# IV_Swinger_2_ss_cell.net
KiCad netlist of a schematic drawn in EAGLE
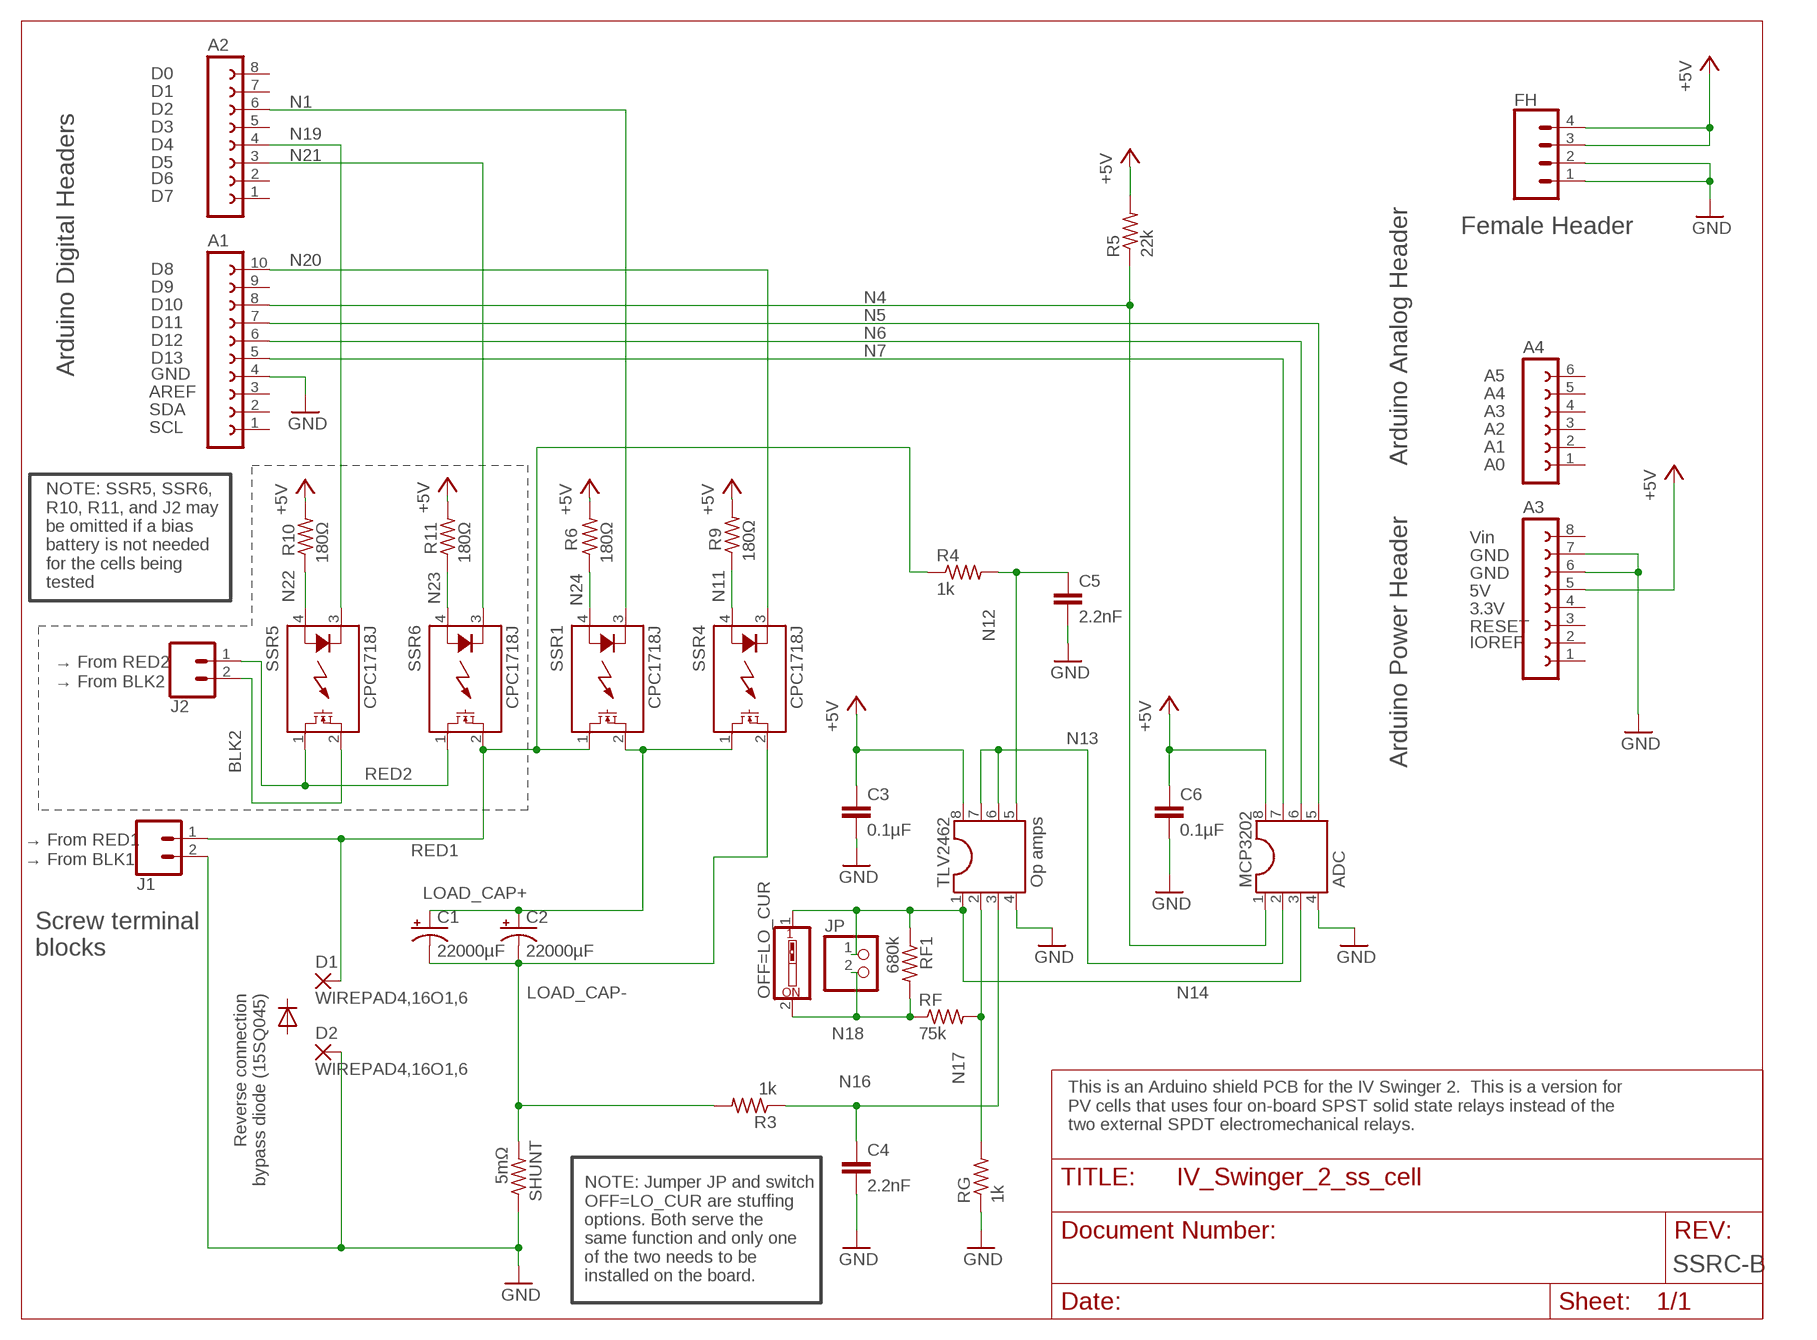
[diagram p0: schematic, sheet 1]

(export (version "E")
  (design (tool "Eeschema 10.0.6"))
  (components
    (comp (ref "A1")
      (value "FE10-1")
      (footprint "eagle-import:FE10")
      (libsource (lib "eagle-import") (part "FE10-1"))
    )
    (comp (ref "A2")
      (value "FE08-1")
      (footprint "eagle-import:FE08")
      (libsource (lib "eagle-import") (part "FE08-1"))
    )
    (comp (ref "A3")
      (value "FE08-1")
      (footprint "eagle-import:FE08")
      (libsource (lib "eagle-import") (part "FE08-1"))
    )
    (comp (ref "A4")
      (value "FE06-1")
      (footprint "eagle-import:FE06")
      (libsource (lib "eagle-import") (part "FE06-1"))
    )
    (comp (ref "C1")
      (value "22000µF")
      (footprint "eagle-import:E7,5-18")
      (libsource (lib "eagle-import") (part "CPOL-USE7.5-18"))
    )
    (comp (ref "C2")
      (value "22000µF")
      (footprint "eagle-import:E7,5-18")
      (libsource (lib "eagle-import") (part "CPOL-USE7.5-18"))
    )
    (comp (ref "C3")
      (value "0.1µF")
      (footprint "eagle-import:C025-030X050")
      (libsource (lib "eagle-import") (part "C-EU025-030X050"))
    )
    (comp (ref "C4")
      (value "2.2nF")
      (footprint "eagle-import:C025-030X050")
      (libsource (lib "eagle-import") (part "C-EU025-030X050"))
    )
    (comp (ref "C5")
      (value "2.2nF")
      (footprint "eagle-import:C025-030X050")
      (libsource (lib "eagle-import") (part "C-EU025-030X050"))
    )
    (comp (ref "C6")
      (value "0.1µF")
      (footprint "eagle-import:C025-030X050")
      (libsource (lib "eagle-import") (part "C-EU025-030X050"))
    )
    (comp (ref "D1")
      (value "WIREPAD4,16O1,6")
      (footprint "eagle-import:4,16O1,6")
      (fields (field (name "SPICEPREFIX") "X"))
      (libsource (lib "eagle-import") (part "WIREPAD4,16O1,6"))
    )
    (comp (ref "D2")
      (value "WIREPAD4,16O1,6")
      (footprint "eagle-import:4,16O1,6")
      (libsource (lib "eagle-import") (part "WIREPAD4,16O1,6"))
    )
    (comp (ref "FH")
      (value "CONN_04LONGPADS")
      (footprint "eagle-import:1X04_LONGPADS")
      (libsource (lib "eagle-import") (part "CONN_04LONGPADS"))
    )
    (comp (ref "J1")
      (value "CONN_025MM")
      (footprint "eagle-import:SCREWTERMINAL-5MM-2")
      (libsource (lib "eagle-import") (part "CONN_025MM"))
    )
    (comp (ref "J2")
      (value "CONN_025MM")
      (footprint "eagle-import:SCREWTERMINAL-5MM-2")
      (libsource (lib "eagle-import") (part "CONN_025MM"))
    )
    (comp (ref "JP")
      (value "PINHD-1X2")
      (footprint "eagle-import:1X02")
      (libsource (lib "eagle-import") (part "PINHD-1X2"))
    )
    (comp (ref "MCP3202")
      (value "ADC")
      (footprint "eagle-import:SOCKET-08")
      (libsource (lib "eagle-import") (part "DIL8S"))
    )
    (comp (ref "OFF=LO_CUR")
      (value "SW_DIP-1")
      (footprint "eagle-import:EDG-01")
      (libsource (lib "eagle-import") (part "SW_DIP-1"))
    )
    (comp (ref "R3")
      (value "1k")
      (footprint "eagle-import:0207_10")
      (libsource (lib "eagle-import") (part "R-US_0207/10"))
    )
    (comp (ref "R4")
      (value "1k")
      (footprint "eagle-import:0207_10")
      (libsource (lib "eagle-import") (part "R-US_0207/10"))
    )
    (comp (ref "R5")
      (value "22k")
      (footprint "eagle-import:0207_10")
      (libsource (lib "eagle-import") (part "R-US_0207/10"))
    )
    (comp (ref "R6")
      (value "180Ω")
      (footprint "eagle-import:0207_10")
      (libsource (lib "eagle-import") (part "R-US_0207/10"))
    )
    (comp (ref "R9")
      (value "180Ω")
      (footprint "eagle-import:0207_10")
      (libsource (lib "eagle-import") (part "R-US_0207/10"))
    )
    (comp (ref "R10")
      (value "180Ω")
      (footprint "eagle-import:0207_10")
      (libsource (lib "eagle-import") (part "R-US_0207/10"))
    )
    (comp (ref "R11")
      (value "180Ω")
      (footprint "eagle-import:0207_10")
      (libsource (lib "eagle-import") (part "R-US_0207/10"))
    )
    (comp (ref "RF")
      (value "75k")
      (footprint "eagle-import:0207_10")
      (libsource (lib "eagle-import") (part "R-US_0207/10"))
    )
    (comp (ref "RF1")
      (value "680k")
      (footprint "eagle-import:0207_10")
      (libsource (lib "eagle-import") (part "R-US_0207/10"))
    )
    (comp (ref "RG")
      (value "1k")
      (footprint "eagle-import:0207_10")
      (libsource (lib "eagle-import") (part "R-US_0207/10"))
    )
    (comp (ref "SHUNT")
      (value "5mΩ")
      (footprint "eagle-import:0617_17")
      (libsource (lib "eagle-import") (part "R-US_0617/17"))
    )
    (comp (ref "SSR1")
      (value "CPC1718J")
      (footprint "eagle-import:I4-PAC")
      (libsource (lib "eagle-import") (part "CPC1718J"))
    )
    (comp (ref "SSR4")
      (value "CPC1718J")
      (footprint "eagle-import:I4-PAC")
      (libsource (lib "eagle-import") (part "CPC1718J"))
    )
    (comp (ref "SSR5")
      (value "CPC1718J")
      (footprint "eagle-import:I4-PAC")
      (libsource (lib "eagle-import") (part "CPC1718J"))
    )
    (comp (ref "SSR6")
      (value "CPC1718J")
      (footprint "eagle-import:I4-PAC")
      (libsource (lib "eagle-import") (part "CPC1718J"))
    )
    (comp (ref "TLV2462")
      (value "Op amps")
      (footprint "eagle-import:SOCKET-08")
      (libsource (lib "eagle-import") (part "DIL8S"))
    )
  )
  (nets
    (net (code "1") (name "+5V") (class "Default")
      (node (ref "A3") (pin "5") (pinfunction "5_5") (pintype "passive"))
      (node (ref "C3") (pin "1") (pinfunction "1_1") (pintype "passive"))
      (node (ref "C6") (pin "1") (pinfunction "1_1") (pintype "passive"))
      (node (ref "FH") (pin "3") (pinfunction "3_3") (pintype "passive"))
      (node (ref "FH") (pin "4") (pinfunction "4_4") (pintype "passive"))
      (node (ref "MCP3202") (pin "8") (pinfunction "8_8") (pintype "passive"))
      (node (ref "R10") (pin "2") (pinfunction "2_2") (pintype "passive"))
      (node (ref "R11") (pin "2") (pinfunction "2_2") (pintype "passive"))
      (node (ref "R5") (pin "2") (pinfunction "2_2") (pintype "passive"))
      (node (ref "R6") (pin "2") (pinfunction "2_2") (pintype "passive"))
      (node (ref "R9") (pin "2") (pinfunction "2_2") (pintype "passive"))
      (node (ref "TLV2462") (pin "8") (pinfunction "8_8") (pintype "passive"))
    )
    (net (code "2") (name "/BLK2") (class "Default")
      (node (ref "J2") (pin "2") (pinfunction "2_2") (pintype "passive"))
      (node (ref "SSR5") (pin "2") (pinfunction "DS2_2") (pintype "passive"))
    )
    (net (code "3") (name "/LOAD_CAP+") (class "Default")
      (node (ref "C1") (pin "+") (pinfunction "+_+") (pintype "passive"))
      (node (ref "C2") (pin "+") (pinfunction "+_+") (pintype "passive"))
      (node (ref "SSR1") (pin "2") (pinfunction "DS2_2") (pintype "passive"))
      (node (ref "SSR4") (pin "1") (pinfunction "DS1_1") (pintype "passive"))
    )
    (net (code "4") (name "/LOAD_CAP-") (class "Default")
      (node (ref "C1") (pin "-") (pinfunction "-_-") (pintype "passive"))
      (node (ref "C2") (pin "-") (pinfunction "-_-") (pintype "passive"))
      (node (ref "R3") (pin "2") (pinfunction "2_2") (pintype "passive"))
      (node (ref "SHUNT") (pin "2") (pinfunction "2_2") (pintype "passive"))
      (node (ref "SSR4") (pin "2") (pinfunction "DS2_2") (pintype "passive"))
    )
    (net (code "5") (name "/N1") (class "Default")
      (node (ref "A2") (pin "6") (pinfunction "6_6") (pintype "passive"))
      (node (ref "SSR1") (pin "3") (pinfunction "K_3") (pintype "passive"))
    )
    (net (code "6") (name "/N4") (class "Default")
      (node (ref "A1") (pin "8") (pinfunction "8_8") (pintype "passive"))
      (node (ref "MCP3202") (pin "1") (pinfunction "1_1") (pintype "passive"))
      (node (ref "R5") (pin "1") (pinfunction "1_1") (pintype "passive"))
    )
    (net (code "7") (name "/N5") (class "Default")
      (node (ref "A1") (pin "7") (pinfunction "7_7") (pintype "passive"))
      (node (ref "MCP3202") (pin "5") (pinfunction "5_5") (pintype "passive"))
    )
    (net (code "8") (name "/N6") (class "Default")
      (node (ref "A1") (pin "6") (pinfunction "6_6") (pintype "passive"))
      (node (ref "MCP3202") (pin "6") (pinfunction "6_6") (pintype "passive"))
    )
    (net (code "9") (name "/N7") (class "Default")
      (node (ref "A1") (pin "5") (pinfunction "5_5") (pintype "passive"))
      (node (ref "MCP3202") (pin "7") (pinfunction "7_7") (pintype "passive"))
    )
    (net (code "10") (name "/N11") (class "Default")
      (node (ref "R9") (pin "1") (pinfunction "1_1") (pintype "passive"))
      (node (ref "SSR4") (pin "4") (pinfunction "A_4") (pintype "passive"))
    )
    (net (code "11") (name "/N12") (class "Default")
      (node (ref "C5") (pin "1") (pinfunction "1_1") (pintype "passive"))
      (node (ref "R4") (pin "2") (pinfunction "2_2") (pintype "passive"))
      (node (ref "TLV2462") (pin "5") (pinfunction "5_5") (pintype "passive"))
    )
    (net (code "12") (name "/N13") (class "Default")
      (node (ref "MCP3202") (pin "2") (pinfunction "2_2") (pintype "passive"))
      (node (ref "TLV2462") (pin "6") (pinfunction "6_6") (pintype "passive"))
      (node (ref "TLV2462") (pin "7") (pinfunction "7_7") (pintype "passive"))
    )
    (net (code "13") (name "/N14") (class "Default")
      (node (ref "JP") (pin "1") (pinfunction "1_1") (pintype "passive"))
      (node (ref "MCP3202") (pin "3") (pinfunction "3_3") (pintype "passive"))
      (node (ref "OFF=LO_CUR") (pin "1") (pinfunction "1_1") (pintype "passive"))
      (node (ref "RF1") (pin "1") (pinfunction "1_1") (pintype "passive"))
      (node (ref "TLV2462") (pin "1") (pinfunction "1_1") (pintype "passive"))
    )
    (net (code "14") (name "/N16") (class "Default")
      (node (ref "C4") (pin "1") (pinfunction "1_1") (pintype "passive"))
      (node (ref "R3") (pin "1") (pinfunction "1_1") (pintype "passive"))
      (node (ref "TLV2462") (pin "3") (pinfunction "3_3") (pintype "passive"))
    )
    (net (code "15") (name "/N17") (class "Default")
      (node (ref "RF") (pin "2") (pinfunction "2_2") (pintype "passive"))
      (node (ref "RG") (pin "2") (pinfunction "2_2") (pintype "passive"))
      (node (ref "TLV2462") (pin "2") (pinfunction "2_2") (pintype "passive"))
    )
    (net (code "16") (name "/N18") (class "Default")
      (node (ref "JP") (pin "2") (pinfunction "2_2") (pintype "passive"))
      (node (ref "OFF=LO_CUR") (pin "2") (pinfunction "2_2") (pintype "passive"))
      (node (ref "RF") (pin "1") (pinfunction "1_1") (pintype "passive"))
      (node (ref "RF1") (pin "2") (pinfunction "2_2") (pintype "passive"))
    )
    (net (code "17") (name "/N19") (class "Default")
      (node (ref "A2") (pin "4") (pinfunction "4_4") (pintype "passive"))
      (node (ref "SSR5") (pin "3") (pinfunction "K_3") (pintype "passive"))
    )
    (net (code "18") (name "/N20") (class "Default")
      (node (ref "A1") (pin "10") (pinfunction "10_10") (pintype "passive"))
      (node (ref "SSR4") (pin "3") (pinfunction "K_3") (pintype "passive"))
    )
    (net (code "19") (name "/N21") (class "Default")
      (node (ref "A2") (pin "3") (pinfunction "3_3") (pintype "passive"))
      (node (ref "SSR6") (pin "3") (pinfunction "K_3") (pintype "passive"))
    )
    (net (code "20") (name "/N22") (class "Default")
      (node (ref "R10") (pin "1") (pinfunction "1_1") (pintype "passive"))
      (node (ref "SSR5") (pin "4") (pinfunction "A_4") (pintype "passive"))
    )
    (net (code "21") (name "/N23") (class "Default")
      (node (ref "R11") (pin "1") (pinfunction "1_1") (pintype "passive"))
      (node (ref "SSR6") (pin "4") (pinfunction "A_4") (pintype "passive"))
    )
    (net (code "22") (name "/N24") (class "Default")
      (node (ref "R6") (pin "1") (pinfunction "1_1") (pintype "passive"))
      (node (ref "SSR1") (pin "4") (pinfunction "A_4") (pintype "passive"))
    )
    (net (code "23") (name "/RED1") (class "Default")
      (node (ref "D1") (pin "1") (pinfunction "P_1") (pintype "passive"))
      (node (ref "J1") (pin "1") (pinfunction "1_1") (pintype "passive"))
      (node (ref "R4") (pin "1") (pinfunction "1_1") (pintype "passive"))
      (node (ref "SSR1") (pin "1") (pinfunction "DS1_1") (pintype "passive"))
      (node (ref "SSR6") (pin "2") (pinfunction "DS2_2") (pintype "passive"))
    )
    (net (code "24") (name "/RED2") (class "Default")
      (node (ref "J2") (pin "1") (pinfunction "1_1") (pintype "passive"))
      (node (ref "SSR5") (pin "1") (pinfunction "DS1_1") (pintype "passive"))
      (node (ref "SSR6") (pin "1") (pinfunction "DS1_1") (pintype "passive"))
    )
    (net (code "25") (name "GND") (class "Default")
      (node (ref "A1") (pin "4") (pinfunction "4_4") (pintype "passive"))
      (node (ref "A3") (pin "6") (pinfunction "6_6") (pintype "passive"))
      (node (ref "A3") (pin "7") (pinfunction "7_7") (pintype "passive"))
      (node (ref "C3") (pin "2") (pinfunction "2_2") (pintype "passive"))
      (node (ref "C4") (pin "2") (pinfunction "2_2") (pintype "passive"))
      (node (ref "C5") (pin "2") (pinfunction "2_2") (pintype "passive"))
      (node (ref "C6") (pin "2") (pinfunction "2_2") (pintype "passive"))
      (node (ref "D2") (pin "1") (pinfunction "P_1") (pintype "passive"))
      (node (ref "FH") (pin "1") (pinfunction "1_1") (pintype "passive"))
      (node (ref "FH") (pin "2") (pinfunction "2_2") (pintype "passive"))
      (node (ref "J1") (pin "2") (pinfunction "2_2") (pintype "passive"))
      (node (ref "MCP3202") (pin "4") (pinfunction "4_4") (pintype "passive"))
      (node (ref "RG") (pin "1") (pinfunction "1_1") (pintype "passive"))
      (node (ref "SHUNT") (pin "1") (pinfunction "1_1") (pintype "passive"))
      (node (ref "TLV2462") (pin "4") (pinfunction "4_4") (pintype "passive"))
    )
    (net (code "26") (name "unconnected-(A1-Pad1)") (class "Default")
      (node (ref "A1") (pin "1") (pinfunction "1_1") (pintype "passive"))
    )
    (net (code "27") (name "unconnected-(A1-Pad2)") (class "Default")
      (node (ref "A1") (pin "2") (pinfunction "2_2") (pintype "passive"))
    )
    (net (code "28") (name "unconnected-(A1-Pad3)") (class "Default")
      (node (ref "A1") (pin "3") (pinfunction "3_3") (pintype "passive"))
    )
    (net (code "29") (name "unconnected-(A1-Pad9)") (class "Default")
      (node (ref "A1") (pin "9") (pinfunction "9_9") (pintype "passive"))
    )
    (net (code "30") (name "unconnected-(A2-Pad1)") (class "Default")
      (node (ref "A2") (pin "1") (pinfunction "1_1") (pintype "passive"))
    )
    (net (code "31") (name "unconnected-(A2-Pad2)") (class "Default")
      (node (ref "A2") (pin "2") (pinfunction "2_2") (pintype "passive"))
    )
    (net (code "32") (name "unconnected-(A2-Pad5)") (class "Default")
      (node (ref "A2") (pin "5") (pinfunction "5_5") (pintype "passive"))
    )
    (net (code "33") (name "unconnected-(A2-Pad7)") (class "Default")
      (node (ref "A2") (pin "7") (pinfunction "7_7") (pintype "passive"))
    )
    (net (code "34") (name "unconnected-(A2-Pad8)") (class "Default")
      (node (ref "A2") (pin "8") (pinfunction "8_8") (pintype "passive"))
    )
    (net (code "35") (name "unconnected-(A3-Pad1)") (class "Default")
      (node (ref "A3") (pin "1") (pinfunction "1_1") (pintype "passive"))
    )
    (net (code "36") (name "unconnected-(A3-Pad2)") (class "Default")
      (node (ref "A3") (pin "2") (pinfunction "2_2") (pintype "passive"))
    )
    (net (code "37") (name "unconnected-(A3-Pad3)") (class "Default")
      (node (ref "A3") (pin "3") (pinfunction "3_3") (pintype "passive"))
    )
    (net (code "38") (name "unconnected-(A3-Pad4)") (class "Default")
      (node (ref "A3") (pin "4") (pinfunction "4_4") (pintype "passive"))
    )
    (net (code "39") (name "unconnected-(A3-Pad8)") (class "Default")
      (node (ref "A3") (pin "8") (pinfunction "8_8") (pintype "passive"))
    )
    (net (code "40") (name "unconnected-(A4-Pad1)") (class "Default")
      (node (ref "A4") (pin "1") (pinfunction "1_1") (pintype "passive"))
    )
    (net (code "41") (name "unconnected-(A4-Pad2)") (class "Default")
      (node (ref "A4") (pin "2") (pinfunction "2_2") (pintype "passive"))
    )
    (net (code "42") (name "unconnected-(A4-Pad3)") (class "Default")
      (node (ref "A4") (pin "3") (pinfunction "3_3") (pintype "passive"))
    )
    (net (code "43") (name "unconnected-(A4-Pad4)") (class "Default")
      (node (ref "A4") (pin "4") (pinfunction "4_4") (pintype "passive"))
    )
    (net (code "44") (name "unconnected-(A4-Pad5)") (class "Default")
      (node (ref "A4") (pin "5") (pinfunction "5_5") (pintype "passive"))
    )
    (net (code "45") (name "unconnected-(A4-Pad6)") (class "Default")
      (node (ref "A4") (pin "6") (pinfunction "6_6") (pintype "passive"))
    )
  )
)
